# SwiftV2.net
KiCad netlist of a schematic drawn in EAGLE
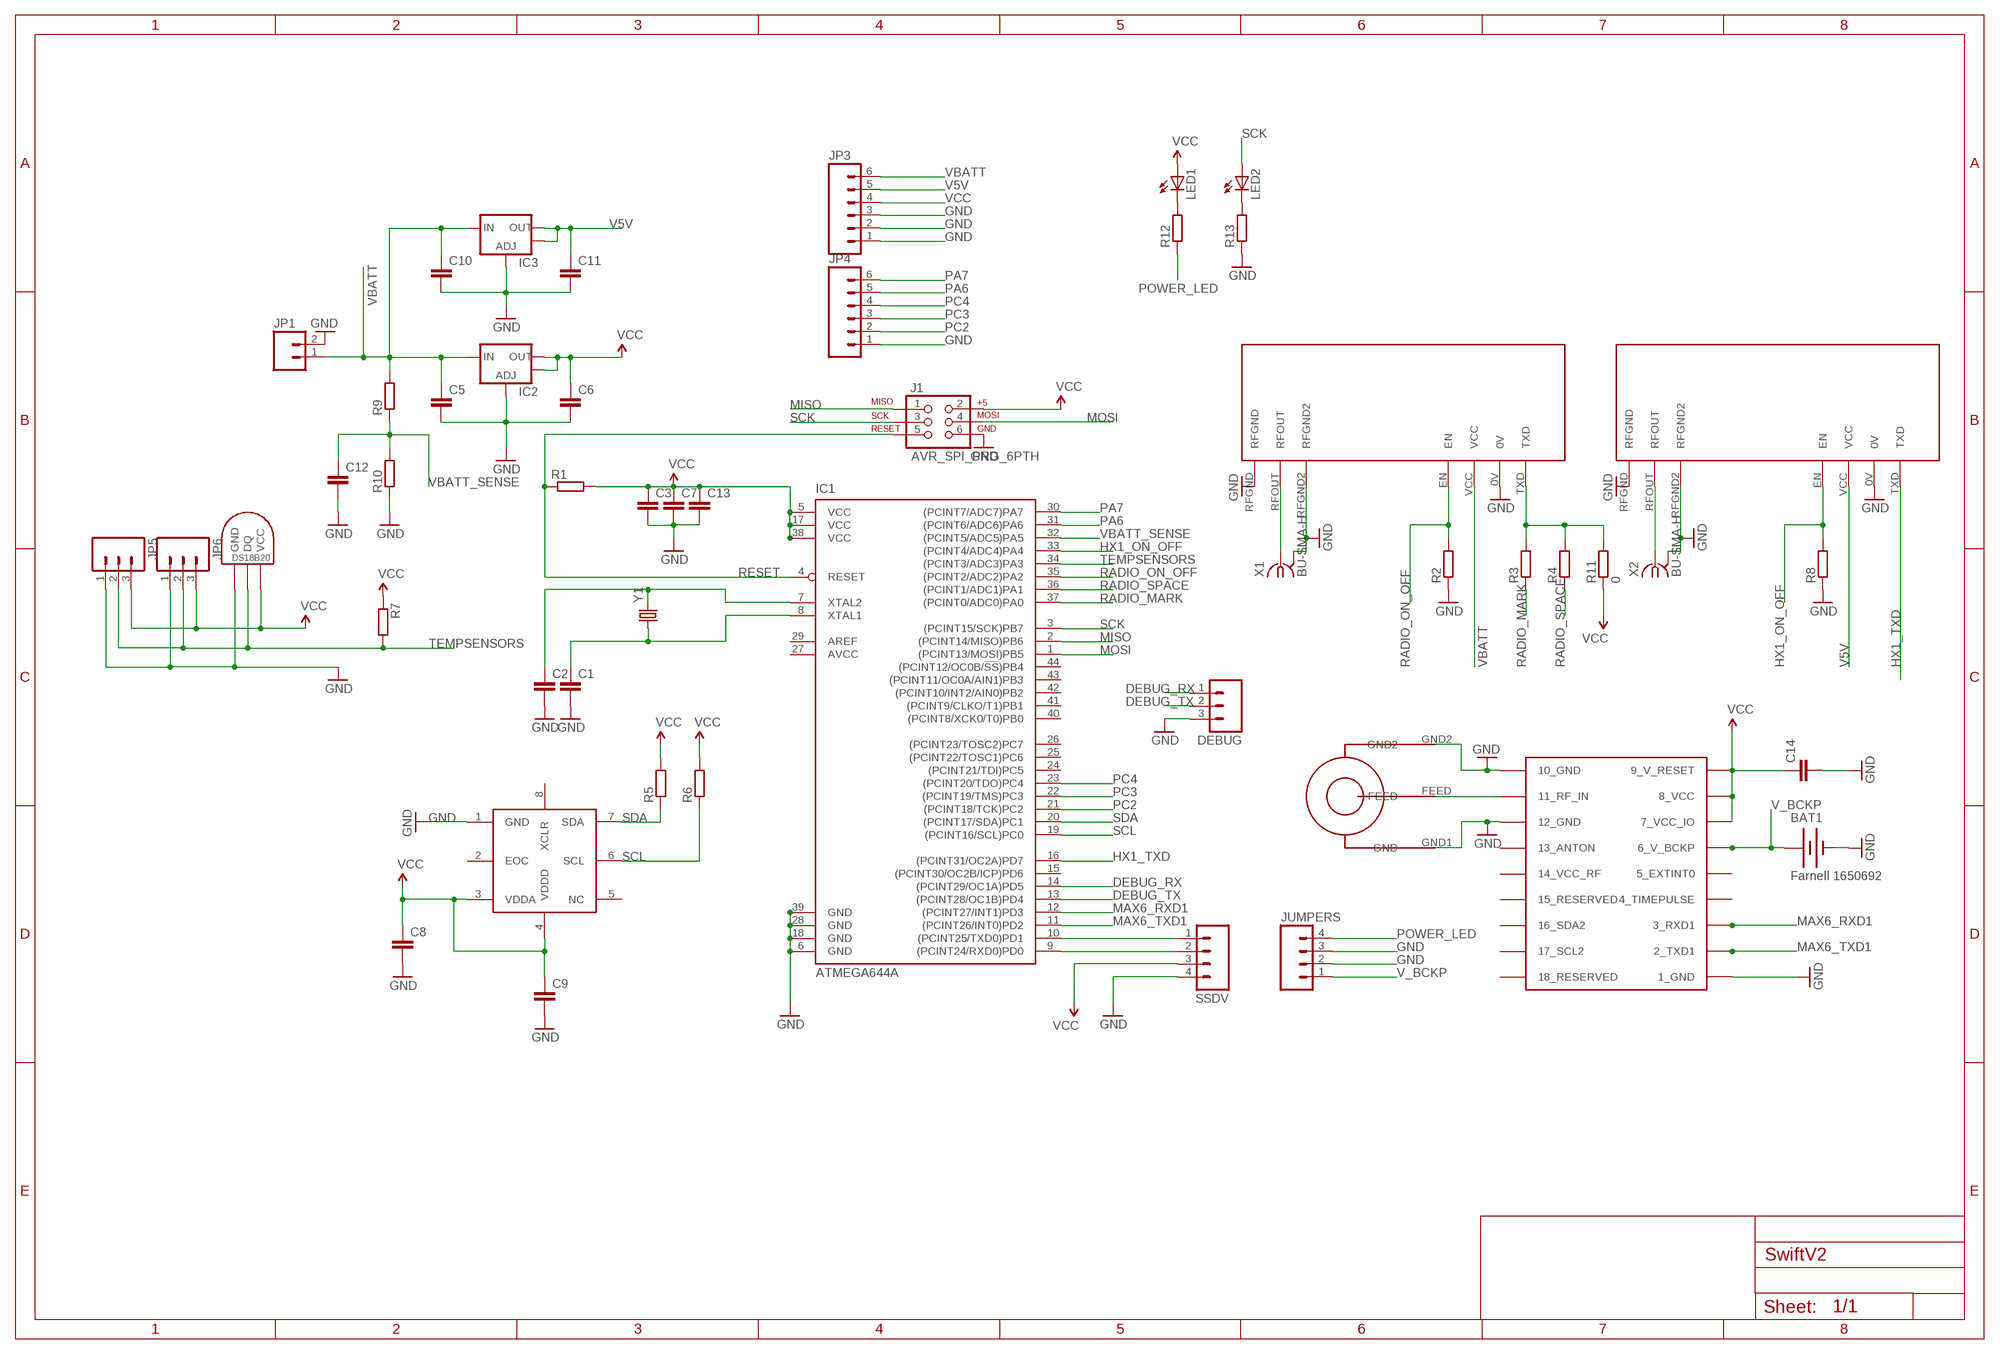
[diagram p0: schematic, sheet 1]

(export (version "E")
  (design (tool "Eeschema 10.0.6"))
  (components
    (comp (ref "BAT1")
      (value "Farnell 1650692")
      (footprint "eagle-import:BATTCON_12MM")
      (libsource (lib "eagle-import") (part "BATTERY12MM"))
    )
    (comp (ref "C1")
      (value "C-EUC0805")
      (footprint "eagle-import:C0805")
      (libsource (lib "eagle-import") (part "C-EUC0805"))
    )
    (comp (ref "C2")
      (value "C-EUC0805")
      (footprint "eagle-import:C0805")
      (libsource (lib "eagle-import") (part "C-EUC0805"))
    )
    (comp (ref "C3")
      (value "C-EUC0805")
      (footprint "eagle-import:C0805")
      (libsource (lib "eagle-import") (part "C-EUC0805"))
    )
    (comp (ref "C5")
      (value "C-EUC0805")
      (footprint "eagle-import:C0805")
      (libsource (lib "eagle-import") (part "C-EUC0805"))
    )
    (comp (ref "C6")
      (value "C-EUC0805")
      (footprint "eagle-import:C0805")
      (libsource (lib "eagle-import") (part "C-EUC0805"))
    )
    (comp (ref "C7")
      (value "C-EUC0805")
      (footprint "eagle-import:C0805")
      (libsource (lib "eagle-import") (part "C-EUC0805"))
    )
    (comp (ref "C8")
      (value "C-EUC0805")
      (footprint "eagle-import:C0805")
      (libsource (lib "eagle-import") (part "C-EUC0805"))
    )
    (comp (ref "C9")
      (value "C-EUC0805")
      (footprint "eagle-import:C0805")
      (libsource (lib "eagle-import") (part "C-EUC0805"))
    )
    (comp (ref "C10")
      (value "C-EUC0805")
      (footprint "eagle-import:C0805")
      (libsource (lib "eagle-import") (part "C-EUC0805"))
    )
    (comp (ref "C11")
      (value "C-EUC0805")
      (footprint "eagle-import:C0805")
      (libsource (lib "eagle-import") (part "C-EUC0805"))
    )
    (comp (ref "C12")
      (value "C-EUC0805")
      (footprint "eagle-import:C0805")
      (libsource (lib "eagle-import") (part "C-EUC0805"))
    )
    (comp (ref "C13")
      (value "C-EUC0805")
      (footprint "eagle-import:C0805")
      (libsource (lib "eagle-import") (part "C-EUC0805"))
    )
    (comp (ref "C14")
      (value "C-EUC0805")
      (footprint "eagle-import:C0805")
      (libsource (lib "eagle-import") (part "C-EUC0805"))
    )
    (comp (ref "DEBUG")
      (value "M03PTH")
      (footprint "eagle-import:1X03")
      (libsource (lib "eagle-import") (part "M03PTH"))
    )
    (comp (ref "IC1")
      (value "ATMEGA644A")
      (footprint "eagle-import:TQFP44")
      (fields (field (name "MPN") "ATMEGA644PV-10AU"))
      (libsource (lib "eagle-import") (part "ATMEGA644A"))
    )
    (comp (ref "IC2")
      (value "V_REG_LM1117SOT223")
      (footprint "eagle-import:SOT223")
      (libsource (lib "eagle-import") (part "V_REG_LM1117SOT223"))
    )
    (comp (ref "IC3")
      (value "V_REG_LM1117SOT223")
      (footprint "eagle-import:SOT223")
      (libsource (lib "eagle-import") (part "V_REG_LM1117SOT223"))
    )
    (comp (ref "J1")
      (value "AVR_SPI_PRG_6PTH")
      (footprint "eagle-import:2X3")
      (libsource (lib "eagle-import") (part "AVR_SPI_PRG_6PTH"))
    )
    (comp (ref "JP1")
      (value "M02JST-PTH-2")
      (footprint "eagle-import:JST-2-PTH")
      (libsource (lib "eagle-import") (part "M02JST-PTH-2"))
    )
    (comp (ref "JP3")
      (value "M06SIP")
      (footprint "eagle-import:1X06")
      (libsource (lib "eagle-import") (part "M06SIP"))
    )
    (comp (ref "JP4")
      (value "M06SIP")
      (footprint "eagle-import:1X06")
      (libsource (lib "eagle-import") (part "M06SIP"))
    )
    (comp (ref "JP5")
      (value "M03JST-PTH")
      (footprint "eagle-import:JST-3-PTH")
      (libsource (lib "eagle-import") (part "M03JST-PTH"))
    )
    (comp (ref "JP6")
      (value "M03JST-PTH")
      (footprint "eagle-import:JST-3-PTH")
      (libsource (lib "eagle-import") (part "M03JST-PTH"))
    )
    (comp (ref "JUMPERS")
      (value "M04PTH")
      (footprint "eagle-import:1X04")
      (libsource (lib "eagle-import") (part "M04PTH"))
    )
    (comp (ref "LED1")
      (value "LED0603")
      (footprint "eagle-import:LED-0603")
      (libsource (lib "eagle-import") (part "LED0603"))
    )
    (comp (ref "LED2")
      (value "LED0603")
      (footprint "eagle-import:LED-0603")
      (libsource (lib "eagle-import") (part "LED0603"))
    )
    (comp (ref "R1")
      (value "R-EU_R0805")
      (footprint "eagle-import:R0805")
      (libsource (lib "eagle-import") (part "R-EU_R0805"))
    )
    (comp (ref "R2")
      (value "R-EU_R0805")
      (footprint "eagle-import:R0805")
      (libsource (lib "eagle-import") (part "R-EU_R0805"))
    )
    (comp (ref "R3")
      (value "R-EU_R0805")
      (footprint "eagle-import:R0805")
      (libsource (lib "eagle-import") (part "R-EU_R0805"))
    )
    (comp (ref "R4")
      (value "R-EU_R0805")
      (footprint "eagle-import:R0805")
      (libsource (lib "eagle-import") (part "R-EU_R0805"))
    )
    (comp (ref "R5")
      (value "R-EU_R0805")
      (footprint "eagle-import:R0805")
      (libsource (lib "eagle-import") (part "R-EU_R0805"))
    )
    (comp (ref "R6")
      (value "R-EU_R0805")
      (footprint "eagle-import:R0805")
      (libsource (lib "eagle-import") (part "R-EU_R0805"))
    )
    (comp (ref "R7")
      (value "R-EU_R0805")
      (footprint "eagle-import:R0805")
      (libsource (lib "eagle-import") (part "R-EU_R0805"))
    )
    (comp (ref "R8")
      (value "R-EU_R0805")
      (footprint "eagle-import:R0805")
      (libsource (lib "eagle-import") (part "R-EU_R0805"))
    )
    (comp (ref "R9")
      (value "R-EU_R0805")
      (footprint "eagle-import:R0805")
      (libsource (lib "eagle-import") (part "R-EU_R0805"))
    )
    (comp (ref "R10")
      (value "R-EU_R0805")
      (footprint "eagle-import:R0805")
      (libsource (lib "eagle-import") (part "R-EU_R0805"))
    )
    (comp (ref "R11")
      (value "0")
      (footprint "eagle-import:R0805")
      (libsource (lib "eagle-import") (part "R-EU_R0805"))
    )
    (comp (ref "R12")
      (value "R-EU_R0805")
      (footprint "eagle-import:R0805")
      (libsource (lib "eagle-import") (part "R-EU_R0805"))
    )
    (comp (ref "R13")
      (value "R-EU_R0805")
      (footprint "eagle-import:R0805")
      (libsource (lib "eagle-import") (part "R-EU_R0805"))
    )
    (comp (ref "SSDV")
      (value "M04PTH")
      (footprint "eagle-import:1X04")
      (libsource (lib "eagle-import") (part "M04PTH"))
    )
    (comp (ref "TEMPINT")
      (value "DS1821")
      (footprint "eagle-import:DS18B20_SOIC")
      (libsource (lib "eagle-import") (part "DS1820SOIC"))
    )
    (comp (ref "U$1")
      (value "BMP085")
      (footprint "eagle-import:BMP085")
      (libsource (lib "eagle-import") (part "BMP085"))
    )
    (comp (ref "U$2")
      (value "NTX2")
      (footprint "eagle-import:NTX2")
      (libsource (lib "eagle-import") (part "NTX2"))
    )
    (comp (ref "U$3")
      (value "SARANTEL-SR1202")
      (footprint "eagle-import:SARANTEL-SR1202")
      (libsource (lib "eagle-import") (part "SARANTEL-SR1202"))
    )
    (comp (ref "U$4")
      (value "UBLOX_MAX-6")
      (footprint "eagle-import:UBLOX_MAX-6")
      (libsource (lib "eagle-import") (part "UBLOX_MAX-6"))
    )
    (comp (ref "U$5")
      (value "RADIOMETRIX-HX1")
      (footprint "eagle-import:RADIOMETRIX-HX1")
      (libsource (lib "eagle-import") (part "RADIOMETRIX-HX1"))
    )
    (comp (ref "X1")
      (value "BU-SMA-H")
      (footprint "eagle-import:BU-SMA-H")
      (libsource (lib "eagle-import") (part "BU-SMA-H"))
    )
    (comp (ref "X2")
      (value "BU-SMA-H")
      (footprint "eagle-import:BU-SMA-H")
      (libsource (lib "eagle-import") (part "BU-SMA-H"))
    )
    (comp (ref "Y1")
      (value "CRYSTALSMD")
      (footprint "eagle-import:HC49UP")
      (libsource (lib "eagle-import") (part "CRYSTALSMD"))
    )
  )
  (nets
    (net (code "1") (name "/AVCC") (class "Default")
      (node (ref "IC1") (pin "27") (pinfunction "AVCC_27") (pintype "power_in"))
    )
    (net (code "2") (name "/DEBUG_RX") (class "Default")
      (node (ref "DEBUG") (pin "1") (pinfunction "1_1") (pintype "passive"))
      (node (ref "IC1") (pin "14") (pinfunction "(PCINT29/OC1A)PD5_14") (pintype "bidirectional"))
    )
    (net (code "3") (name "/DEBUG_TX") (class "Default")
      (node (ref "DEBUG") (pin "2") (pinfunction "2_2") (pintype "passive"))
      (node (ref "IC1") (pin "13") (pinfunction "(PCINT28/OC1B)PD4_13") (pintype "bidirectional"))
    )
    (net (code "4") (name "/HX1_ON_OFF") (class "Default")
      (node (ref "IC1") (pin "33") (pinfunction "(PCINT4/ADC4)PA4_33") (pintype "bidirectional"))
      (node (ref "R8") (pin "2") (pinfunction "2_2") (pintype "passive"))
      (node (ref "U$5") (pin "EN") (pinfunction "EN_EN") (pintype "bidirectional"))
    )
    (net (code "5") (name "/HX1_TXD") (class "Default")
      (node (ref "IC1") (pin "16") (pinfunction "(PCINT31/OC2A)PD7_16") (pintype "bidirectional"))
      (node (ref "U$5") (pin "TXD") (pinfunction "TXD_TXD") (pintype "bidirectional"))
    )
    (net (code "6") (name "/MAX6_RXD1") (class "Default")
      (node (ref "IC1") (pin "12") (pinfunction "(PCINT27/INT1)PD3_12") (pintype "bidirectional"))
      (node (ref "U$4") (pin "3_RXD1") (pinfunction "3_RXD1_3_RXD1") (pintype "bidirectional"))
    )
    (net (code "7") (name "/MAX6_TXD1") (class "Default")
      (node (ref "IC1") (pin "11") (pinfunction "(PCINT26/INT0)PD2_11") (pintype "bidirectional"))
      (node (ref "U$4") (pin "2_TXD1") (pinfunction "2_TXD1_2_TXD1") (pintype "bidirectional"))
    )
    (net (code "8") (name "/MISO") (class "Default")
      (node (ref "IC1") (pin "2") (pinfunction "(PCINT14/MISO)PB6_2") (pintype "bidirectional"))
      (node (ref "J1") (pin "1") (pinfunction "1_1") (pintype "passive"))
    )
    (net (code "9") (name "/MOSI") (class "Default")
      (node (ref "IC1") (pin "1") (pinfunction "(PCINT13/MOSI)PB5_1") (pintype "bidirectional"))
      (node (ref "J1") (pin "4") (pinfunction "4_4") (pintype "passive"))
    )
    (net (code "10") (name "/PA6") (class "Default")
      (node (ref "IC1") (pin "31") (pinfunction "(PCINT6/ADC6)PA6_31") (pintype "bidirectional"))
      (node (ref "JP4") (pin "5") (pinfunction "5_5") (pintype "passive"))
    )
    (net (code "11") (name "/PA7") (class "Default")
      (node (ref "IC1") (pin "30") (pinfunction "(PCINT7/ADC7)PA7_30") (pintype "bidirectional"))
      (node (ref "JP4") (pin "6") (pinfunction "6_6") (pintype "passive"))
    )
    (net (code "12") (name "/PC2") (class "Default")
      (node (ref "IC1") (pin "21") (pinfunction "(PCINT18/TCK)PC2_21") (pintype "output"))
      (node (ref "JP4") (pin "2") (pinfunction "2_2") (pintype "passive"))
    )
    (net (code "13") (name "/PC3") (class "Default")
      (node (ref "IC1") (pin "22") (pinfunction "(PCINT19/TMS)PC3_22") (pintype "output"))
      (node (ref "JP4") (pin "3") (pinfunction "3_3") (pintype "passive"))
    )
    (net (code "14") (name "/PC4") (class "Default")
      (node (ref "IC1") (pin "23") (pinfunction "(PCINT20/TDO)PC4_23") (pintype "output"))
      (node (ref "JP4") (pin "4") (pinfunction "4_4") (pintype "passive"))
    )
    (net (code "15") (name "/POWER_LED") (class "Default")
      (node (ref "JUMPERS") (pin "4") (pinfunction "4_4") (pintype "passive"))
      (node (ref "R12") (pin "1") (pinfunction "1_1") (pintype "passive"))
    )
    (net (code "16") (name "/RADIO_MARK") (class "Default")
      (node (ref "IC1") (pin "37") (pinfunction "(PCINT0/ADC0)PA0_37") (pintype "bidirectional"))
      (node (ref "R3") (pin "1") (pinfunction "1_1") (pintype "passive"))
    )
    (net (code "17") (name "/RADIO_ON_OFF") (class "Default")
      (node (ref "IC1") (pin "35") (pinfunction "(PCINT2/ADC2)PA2_35") (pintype "bidirectional"))
      (node (ref "R2") (pin "2") (pinfunction "2_2") (pintype "passive"))
      (node (ref "U$2") (pin "EN") (pinfunction "EN_EN") (pintype "bidirectional"))
    )
    (net (code "18") (name "/RADIO_SPACE") (class "Default")
      (node (ref "IC1") (pin "36") (pinfunction "(PCINT1/ADC1)PA1_36") (pintype "bidirectional"))
      (node (ref "R4") (pin "1") (pinfunction "1_1") (pintype "passive"))
    )
    (net (code "19") (name "/RESET") (class "Default")
      (node (ref "IC1") (pin "4") (pinfunction "RESET_4") (pintype "input"))
      (node (ref "J1") (pin "5") (pinfunction "5_5") (pintype "passive"))
      (node (ref "R1") (pin "1") (pinfunction "1_1") (pintype "passive"))
    )
    (net (code "20") (name "/SCK") (class "Default")
      (node (ref "IC1") (pin "3") (pinfunction "(PCINT15/SCK)PB7_3") (pintype "bidirectional"))
      (node (ref "J1") (pin "3") (pinfunction "3_3") (pintype "passive"))
      (node (ref "LED2") (pin "A") (pinfunction "A_A") (pintype "passive"))
    )
    (net (code "21") (name "/SCL") (class "Default")
      (node (ref "IC1") (pin "19") (pinfunction "(PCINT16/SCL)PC0_19") (pintype "output"))
      (node (ref "R6") (pin "1") (pinfunction "1_1") (pintype "passive"))
      (node (ref "U$1") (pin "6") (pinfunction "SCL_6") (pintype "bidirectional"))
    )
    (net (code "22") (name "/SDA") (class "Default")
      (node (ref "IC1") (pin "20") (pinfunction "(PCINT17/SDA)PC1_20") (pintype "output"))
      (node (ref "R5") (pin "1") (pinfunction "1_1") (pintype "passive"))
      (node (ref "U$1") (pin "7") (pinfunction "SDA_7") (pintype "bidirectional"))
    )
    (net (code "23") (name "/TEMPSENSORS") (class "Default")
      (node (ref "IC1") (pin "34") (pinfunction "(PCINT3/ADC3)PA3_34") (pintype "bidirectional"))
      (node (ref "JP5") (pin "2") (pinfunction "2_2") (pintype "passive"))
      (node (ref "JP6") (pin "2") (pinfunction "2_2") (pintype "passive"))
      (node (ref "R7") (pin "2") (pinfunction "2_2") (pintype "passive"))
      (node (ref "TEMPINT") (pin "DQ") (pinfunction "DQ_DQ") (pintype "bidirectional"))
    )
    (net (code "24") (name "/V5V") (class "Default")
      (node (ref "C11") (pin "1") (pinfunction "1_1") (pintype "passive"))
      (node (ref "IC3") (pin "2") (pinfunction "OUT_2") (pintype "output"))
      (node (ref "IC3") (pin "4") (pinfunction "OUT_4") (pintype "output"))
      (node (ref "JP3") (pin "5") (pinfunction "5_5") (pintype "passive"))
      (node (ref "U$5") (pin "VCC") (pinfunction "VCC_VCC") (pintype "bidirectional"))
    )
    (net (code "25") (name "/VBATT") (class "Default")
      (node (ref "C10") (pin "1") (pinfunction "1_1") (pintype "passive"))
      (node (ref "C5") (pin "1") (pinfunction "1_1") (pintype "passive"))
      (node (ref "IC2") (pin "3") (pinfunction "IN_3") (pintype "input"))
      (node (ref "IC3") (pin "3") (pinfunction "IN_3") (pintype "input"))
      (node (ref "JP1") (pin "1") (pinfunction "1_1") (pintype "passive"))
      (node (ref "JP3") (pin "6") (pinfunction "6_6") (pintype "passive"))
      (node (ref "R9") (pin "2") (pinfunction "2_2") (pintype "passive"))
      (node (ref "U$2") (pin "VCC") (pinfunction "VCC_VCC") (pintype "bidirectional"))
    )
    (net (code "26") (name "/VBATT_SENSE") (class "Default")
      (node (ref "C12") (pin "1") (pinfunction "1_1") (pintype "passive"))
      (node (ref "IC1") (pin "32") (pinfunction "(PCINT5/ADC5)PA5_32") (pintype "bidirectional"))
      (node (ref "R10") (pin "2") (pinfunction "2_2") (pintype "passive"))
      (node (ref "R9") (pin "1") (pinfunction "1_1") (pintype "passive"))
    )
    (net (code "27") (name "/V_BCKP") (class "Default")
      (node (ref "BAT1") (pin "PWR@1") (pinfunction "+_PWR@1") (pintype "power_in"))
      (node (ref "JUMPERS") (pin "1") (pinfunction "1_1") (pintype "passive"))
      (node (ref "U$4") (pin "6_V_BCKP") (pinfunction "6_V_BCKP_6_V_BCKP") (pintype "bidirectional"))
    )
    (net (code "28") (name "GND") (class "Default")
      (node (ref "BAT1") (pin "GND") (pinfunction "-_GND") (pintype "power_in"))
      (node (ref "C1") (pin "2") (pinfunction "2_2") (pintype "passive"))
      (node (ref "C10") (pin "2") (pinfunction "2_2") (pintype "passive"))
      (node (ref "C11") (pin "2") (pinfunction "2_2") (pintype "passive"))
      (node (ref "C12") (pin "2") (pinfunction "2_2") (pintype "passive"))
      (node (ref "C13") (pin "2") (pinfunction "2_2") (pintype "passive"))
      (node (ref "C14") (pin "2") (pinfunction "2_2") (pintype "passive"))
      (node (ref "C2") (pin "2") (pinfunction "2_2") (pintype "passive"))
      (node (ref "C3") (pin "2") (pinfunction "2_2") (pintype "passive"))
      (node (ref "C5") (pin "2") (pinfunction "2_2") (pintype "passive"))
      (node (ref "C6") (pin "2") (pinfunction "2_2") (pintype "passive"))
      (node (ref "C7") (pin "2") (pinfunction "2_2") (pintype "passive"))
      (node (ref "C8") (pin "2") (pinfunction "2_2") (pintype "passive"))
      (node (ref "C9") (pin "2") (pinfunction "2_2") (pintype "passive"))
      (node (ref "DEBUG") (pin "3") (pinfunction "3_3") (pintype "passive"))
      (node (ref "IC1") (pin "18") (pinfunction "GND_18") (pintype "power_in"))
      (node (ref "IC1") (pin "28") (pinfunction "GND_28") (pintype "power_in"))
      (node (ref "IC1") (pin "39") (pinfunction "GND_39") (pintype "power_in"))
      (node (ref "IC1") (pin "6") (pinfunction "GND_6") (pintype "power_in"))
      (node (ref "IC2") (pin "1") (pinfunction "ADJ_1") (pintype "input"))
      (node (ref "IC3") (pin "1") (pinfunction "ADJ_1") (pintype "input"))
      (node (ref "J1") (pin "6") (pinfunction "6_6") (pintype "passive"))
      (node (ref "JP1") (pin "2") (pinfunction "2_2") (pintype "passive"))
      (node (ref "JP3") (pin "1") (pinfunction "1_1") (pintype "passive"))
      (node (ref "JP3") (pin "2") (pinfunction "2_2") (pintype "passive"))
      (node (ref "JP3") (pin "3") (pinfunction "3_3") (pintype "passive"))
      (node (ref "JP4") (pin "1") (pinfunction "1_1") (pintype "passive"))
      (node (ref "JP5") (pin "1") (pinfunction "1_1") (pintype "passive"))
      (node (ref "JP6") (pin "1") (pinfunction "1_1") (pintype "passive"))
      (node (ref "JUMPERS") (pin "2") (pinfunction "2_2") (pintype "passive"))
      (node (ref "JUMPERS") (pin "3") (pinfunction "3_3") (pintype "passive"))
      (node (ref "R10") (pin "1") (pinfunction "1_1") (pintype "passive"))
      (node (ref "R13") (pin "1") (pinfunction "1_1") (pintype "passive"))
      (node (ref "R2") (pin "1") (pinfunction "1_1") (pintype "passive"))
      (node (ref "R8") (pin "1") (pinfunction "1_1") (pintype "passive"))
      (node (ref "SSDV") (pin "4") (pinfunction "4_4") (pintype "passive"))
      (node (ref "TEMPINT") (pin "GND") (pinfunction "GND_GND") (pintype "power_in"))
      (node (ref "U$1") (pin "1") (pinfunction "GND_1") (pintype "bidirectional"))
      (node (ref "U$2") (pin "0V") (pinfunction "0V_0V") (pintype "bidirectional"))
      (node (ref "U$2") (pin "RFGND") (pinfunction "RFGND_RFGND") (pintype "bidirectional"))
      (node (ref "U$2") (pin "RFGND2") (pinfunction "RFGND2_RFGND2") (pintype "bidirectional"))
      (node (ref "U$3") (pin "GND1") (pinfunction "GND_GND1") (pintype "bidirectional"))
      (node (ref "U$3") (pin "GND2") (pinfunction "GND2_GND2") (pintype "bidirectional"))
      (node (ref "U$4") (pin "10_GND") (pinfunction "10_GND_10_GND") (pintype "bidirectional"))
      (node (ref "U$4") (pin "12_GND") (pinfunction "12_GND_12_GND") (pintype "bidirectional"))
      (node (ref "U$4") (pin "1_GND") (pinfunction "1_GND_1_GND") (pintype "bidirectional"))
      (node (ref "U$5") (pin "0V") (pinfunction "0V_0V") (pintype "bidirectional"))
      (node (ref "U$5") (pin "RFGND") (pinfunction "RFGND_RFGND") (pintype "bidirectional"))
      (node (ref "U$5") (pin "RFGND2") (pinfunction "RFGND2_RFGND2") (pintype "bidirectional"))
      (node (ref "X1") (pin "2") (pinfunction "GND_2") (pintype "power_in"))
      (node (ref "X2") (pin "2") (pinfunction "GND_2") (pintype "power_in"))
    )
    (net (code "29") (name "Net-(IC1-(PCINT24{slash}RXD0)PD0)") (class "Default")
      (node (ref "IC1") (pin "9") (pinfunction "(PCINT24/RXD0)PD0_9") (pintype "bidirectional"))
      (node (ref "SSDV") (pin "2") (pinfunction "2_2") (pintype "passive"))
    )
    (net (code "30") (name "Net-(IC1-(PCINT25{slash}TXD0)PD1)") (class "Default")
      (node (ref "IC1") (pin "10") (pinfunction "(PCINT25/TXD0)PD1_10") (pintype "bidirectional"))
      (node (ref "SSDV") (pin "1") (pinfunction "1_1") (pintype "passive"))
    )
    (net (code "31") (name "Net-(IC1-XTAL1)") (class "Default")
      (node (ref "C1") (pin "1") (pinfunction "1_1") (pintype "passive"))
      (node (ref "IC1") (pin "8") (pinfunction "XTAL1_8") (pintype "bidirectional"))
      (node (ref "Y1") (pin "1") (pinfunction "1_1") (pintype "passive"))
    )
    (net (code "32") (name "Net-(IC1-XTAL2)") (class "Default")
      (node (ref "C2") (pin "1") (pinfunction "1_1") (pintype "passive"))
      (node (ref "IC1") (pin "7") (pinfunction "XTAL2_7") (pintype "bidirectional"))
      (node (ref "Y1") (pin "2") (pinfunction "2_2") (pintype "passive"))
    )
    (net (code "33") (name "Net-(LED1-PadC)") (class "Default")
      (node (ref "LED1") (pin "C") (pinfunction "C_C") (pintype "passive"))
      (node (ref "R12") (pin "2") (pinfunction "2_2") (pintype "passive"))
    )
    (net (code "34") (name "Net-(LED2-PadC)") (class "Default")
      (node (ref "LED2") (pin "C") (pinfunction "C_C") (pintype "passive"))
      (node (ref "R13") (pin "2") (pinfunction "2_2") (pintype "passive"))
    )
    (net (code "35") (name "Net-(R11-Pad2)") (class "Default")
      (node (ref "R11") (pin "2") (pinfunction "2_2") (pintype "passive"))
      (node (ref "R3") (pin "2") (pinfunction "2_2") (pintype "passive"))
      (node (ref "R4") (pin "2") (pinfunction "2_2") (pintype "passive"))
      (node (ref "U$2") (pin "TXD") (pinfunction "TXD_TXD") (pintype "bidirectional"))
    )
    (net (code "36") (name "Net-(U$2-PadRFOUT)") (class "Default")
      (node (ref "U$2") (pin "RFOUT") (pinfunction "RFOUT_RFOUT") (pintype "bidirectional"))
      (node (ref "X1") (pin "1") (pinfunction "1_1") (pintype "passive"))
    )
    (net (code "37") (name "Net-(U$3-PadFEED)") (class "Default")
      (node (ref "U$3") (pin "FEED") (pinfunction "FEED_FEED") (pintype "bidirectional"))
      (node (ref "U$4") (pin "11_RF_IN") (pinfunction "11_RF_IN_11_RF_IN") (pintype "bidirectional"))
    )
    (net (code "38") (name "Net-(U$5-PadRFOUT)") (class "Default")
      (node (ref "U$5") (pin "RFOUT") (pinfunction "RFOUT_RFOUT") (pintype "bidirectional"))
      (node (ref "X2") (pin "1") (pinfunction "1_1") (pintype "passive"))
    )
    (net (code "39") (name "VCC") (class "Default")
      (node (ref "C13") (pin "1") (pinfunction "1_1") (pintype "passive"))
      (node (ref "C14") (pin "1") (pinfunction "1_1") (pintype "passive"))
      (node (ref "C3") (pin "1") (pinfunction "1_1") (pintype "passive"))
      (node (ref "C6") (pin "1") (pinfunction "1_1") (pintype "passive"))
      (node (ref "C7") (pin "1") (pinfunction "1_1") (pintype "passive"))
      (node (ref "C8") (pin "1") (pinfunction "1_1") (pintype "passive"))
      (node (ref "C9") (pin "1") (pinfunction "1_1") (pintype "passive"))
      (node (ref "IC1") (pin "17") (pinfunction "VCC_17") (pintype "power_in"))
      (node (ref "IC1") (pin "38") (pinfunction "VCC_38") (pintype "power_in"))
      (node (ref "IC1") (pin "5") (pinfunction "VCC_5") (pintype "power_in"))
      (node (ref "IC2") (pin "2") (pinfunction "OUT_2") (pintype "output"))
      (node (ref "IC2") (pin "4") (pinfunction "OUT_4") (pintype "output"))
      (node (ref "J1") (pin "2") (pinfunction "2_2") (pintype "passive"))
      (node (ref "JP3") (pin "4") (pinfunction "4_4") (pintype "passive"))
      (node (ref "JP5") (pin "3") (pinfunction "3_3") (pintype "passive"))
      (node (ref "JP6") (pin "3") (pinfunction "3_3") (pintype "passive"))
      (node (ref "LED1") (pin "A") (pinfunction "A_A") (pintype "passive"))
      (node (ref "R1") (pin "2") (pinfunction "2_2") (pintype "passive"))
      (node (ref "R11") (pin "1") (pinfunction "1_1") (pintype "passive"))
      (node (ref "R5") (pin "2") (pinfunction "2_2") (pintype "passive"))
      (node (ref "R6") (pin "2") (pinfunction "2_2") (pintype "passive"))
      (node (ref "R7") (pin "1") (pinfunction "1_1") (pintype "passive"))
      (node (ref "SSDV") (pin "3") (pinfunction "3_3") (pintype "passive"))
      (node (ref "TEMPINT") (pin "VCC") (pinfunction "VCC_VCC") (pintype "power_in"))
      (node (ref "U$1") (pin "3") (pinfunction "VDDA_3") (pintype "bidirectional"))
      (node (ref "U$1") (pin "4") (pinfunction "VDDD_4") (pintype "bidirectional"))
      (node (ref "U$4") (pin "7_VCC_IO") (pinfunction "7_VCC_IO_7_VCC_IO") (pintype "bidirectional"))
      (node (ref "U$4") (pin "8_VCC") (pinfunction "8_VCC_8_VCC") (pintype "bidirectional"))
      (node (ref "U$4") (pin "9_V_RESET") (pinfunction "9_V_RESET_9_V_RESET") (pintype "bidirectional"))
    )
    (net (code "40") (name "unconnected-(IC1-(PCINT8{slash}XCK0{slash}T0)PB0-Pad40)") (class "Default")
      (node (ref "IC1") (pin "40") (pinfunction "(PCINT8/XCK0/T0)PB0_40") (pintype "bidirectional"))
    )
    (net (code "41") (name "unconnected-(IC1-(PCINT9{slash}CLKO{slash}T1)PB1-Pad41)") (class "Default")
      (node (ref "IC1") (pin "41") (pinfunction "(PCINT9/CLKO/T1)PB1_41") (pintype "bidirectional"))
    )
    (net (code "42") (name "unconnected-(IC1-(PCINT10{slash}INT2{slash}AIN0)PB2-Pad42)") (class "Default")
      (node (ref "IC1") (pin "42") (pinfunction "(PCINT10/INT2/AIN0)PB2_42") (pintype "bidirectional"))
    )
    (net (code "43") (name "unconnected-(IC1-(PCINT11{slash}OC0A{slash}AIN1)PB3-Pad43)") (class "Default")
      (node (ref "IC1") (pin "43") (pinfunction "(PCINT11/OC0A/AIN1)PB3_43") (pintype "bidirectional"))
    )
    (net (code "44") (name "unconnected-(IC1-(PCINT12{slash}OC0B{slash}~{SS})PB4-Pad44)") (class "Default")
      (node (ref "IC1") (pin "44") (pinfunction "(PCINT12/OC0B/~{SS})PB4_44") (pintype "bidirectional"))
    )
    (net (code "45") (name "unconnected-(IC1-(PCINT21{slash}TDI)PC5-Pad24)") (class "Default")
      (node (ref "IC1") (pin "24") (pinfunction "(PCINT21/TDI)PC5_24") (pintype "output"))
    )
    (net (code "46") (name "unconnected-(IC1-(PCINT22{slash}TOSC1)PC6-Pad25)") (class "Default")
      (node (ref "IC1") (pin "25") (pinfunction "(PCINT22/TOSC1)PC6_25") (pintype "output"))
    )
    (net (code "47") (name "unconnected-(IC1-(PCINT23{slash}TOSC2)PC7-Pad26)") (class "Default")
      (node (ref "IC1") (pin "26") (pinfunction "(PCINT23/TOSC2)PC7_26") (pintype "output"))
    )
    (net (code "48") (name "unconnected-(IC1-(PCINT30{slash}OC2B{slash}ICP)PD6-Pad15)") (class "Default")
      (node (ref "IC1") (pin "15") (pinfunction "(PCINT30/OC2B/ICP)PD6_15") (pintype "bidirectional"))
    )
    (net (code "49") (name "unconnected-(IC1-AREF-Pad29)") (class "Default")
      (node (ref "IC1") (pin "29") (pinfunction "AREF_29") (pintype "passive"))
    )
    (net (code "50") (name "unconnected-(U$1-EOC-Pad2)") (class "Default")
      (node (ref "U$1") (pin "2") (pinfunction "EOC_2") (pintype "bidirectional"))
    )
    (net (code "51") (name "unconnected-(U$1-NC-Pad5)") (class "Default")
      (node (ref "U$1") (pin "5") (pinfunction "NC_5") (pintype "bidirectional"))
    )
    (net (code "52") (name "unconnected-(U$1-XCLR-Pad8)") (class "Default")
      (node (ref "U$1") (pin "8") (pinfunction "XCLR_8") (pintype "bidirectional"))
    )
    (net (code "53") (name "unconnected-(U$4-Pad4_TIMEPULSE)") (class "Default")
      (node (ref "U$4") (pin "4_TIMEPULSE") (pinfunction "4_TIMEPULSE_4_TIMEPULSE") (pintype "bidirectional"))
    )
    (net (code "54") (name "unconnected-(U$4-Pad5_EXTINT0)") (class "Default")
      (node (ref "U$4") (pin "5_EXTINT0") (pinfunction "5_EXTINT0_5_EXTINT0") (pintype "bidirectional"))
    )
    (net (code "55") (name "unconnected-(U$4-Pad13_ANTON)") (class "Default")
      (node (ref "U$4") (pin "13_ANTON") (pinfunction "13_ANTON_13_ANTON") (pintype "bidirectional"))
    )
    (net (code "56") (name "unconnected-(U$4-Pad14_VCC_RF)") (class "Default")
      (node (ref "U$4") (pin "14_VCC_RF") (pinfunction "14_VCC_RF_14_VCC_RF") (pintype "bidirectional"))
    )
    (net (code "57") (name "unconnected-(U$4-Pad15_RESERVED)") (class "Default")
      (node (ref "U$4") (pin "15_RESERVED") (pinfunction "15_RESERVED_15_RESERVED") (pintype "bidirectional"))
    )
    (net (code "58") (name "unconnected-(U$4-Pad16_SDA2)") (class "Default")
      (node (ref "U$4") (pin "16_SDA2") (pinfunction "16_SDA2_16_SDA2") (pintype "bidirectional"))
    )
    (net (code "59") (name "unconnected-(U$4-Pad17_SCL2)") (class "Default")
      (node (ref "U$4") (pin "17_SCL2") (pinfunction "17_SCL2_17_SCL2") (pintype "bidirectional"))
    )
    (net (code "60") (name "unconnected-(U$4-Pad18_RESERVED)") (class "Default")
      (node (ref "U$4") (pin "18_RESERVED") (pinfunction "18_RESERVED_18_RESERVED") (pintype "bidirectional"))
    )
  )
)
